# 12-JLINK_1.net
KiCad netlist of a schematic drawn in Altium Designer
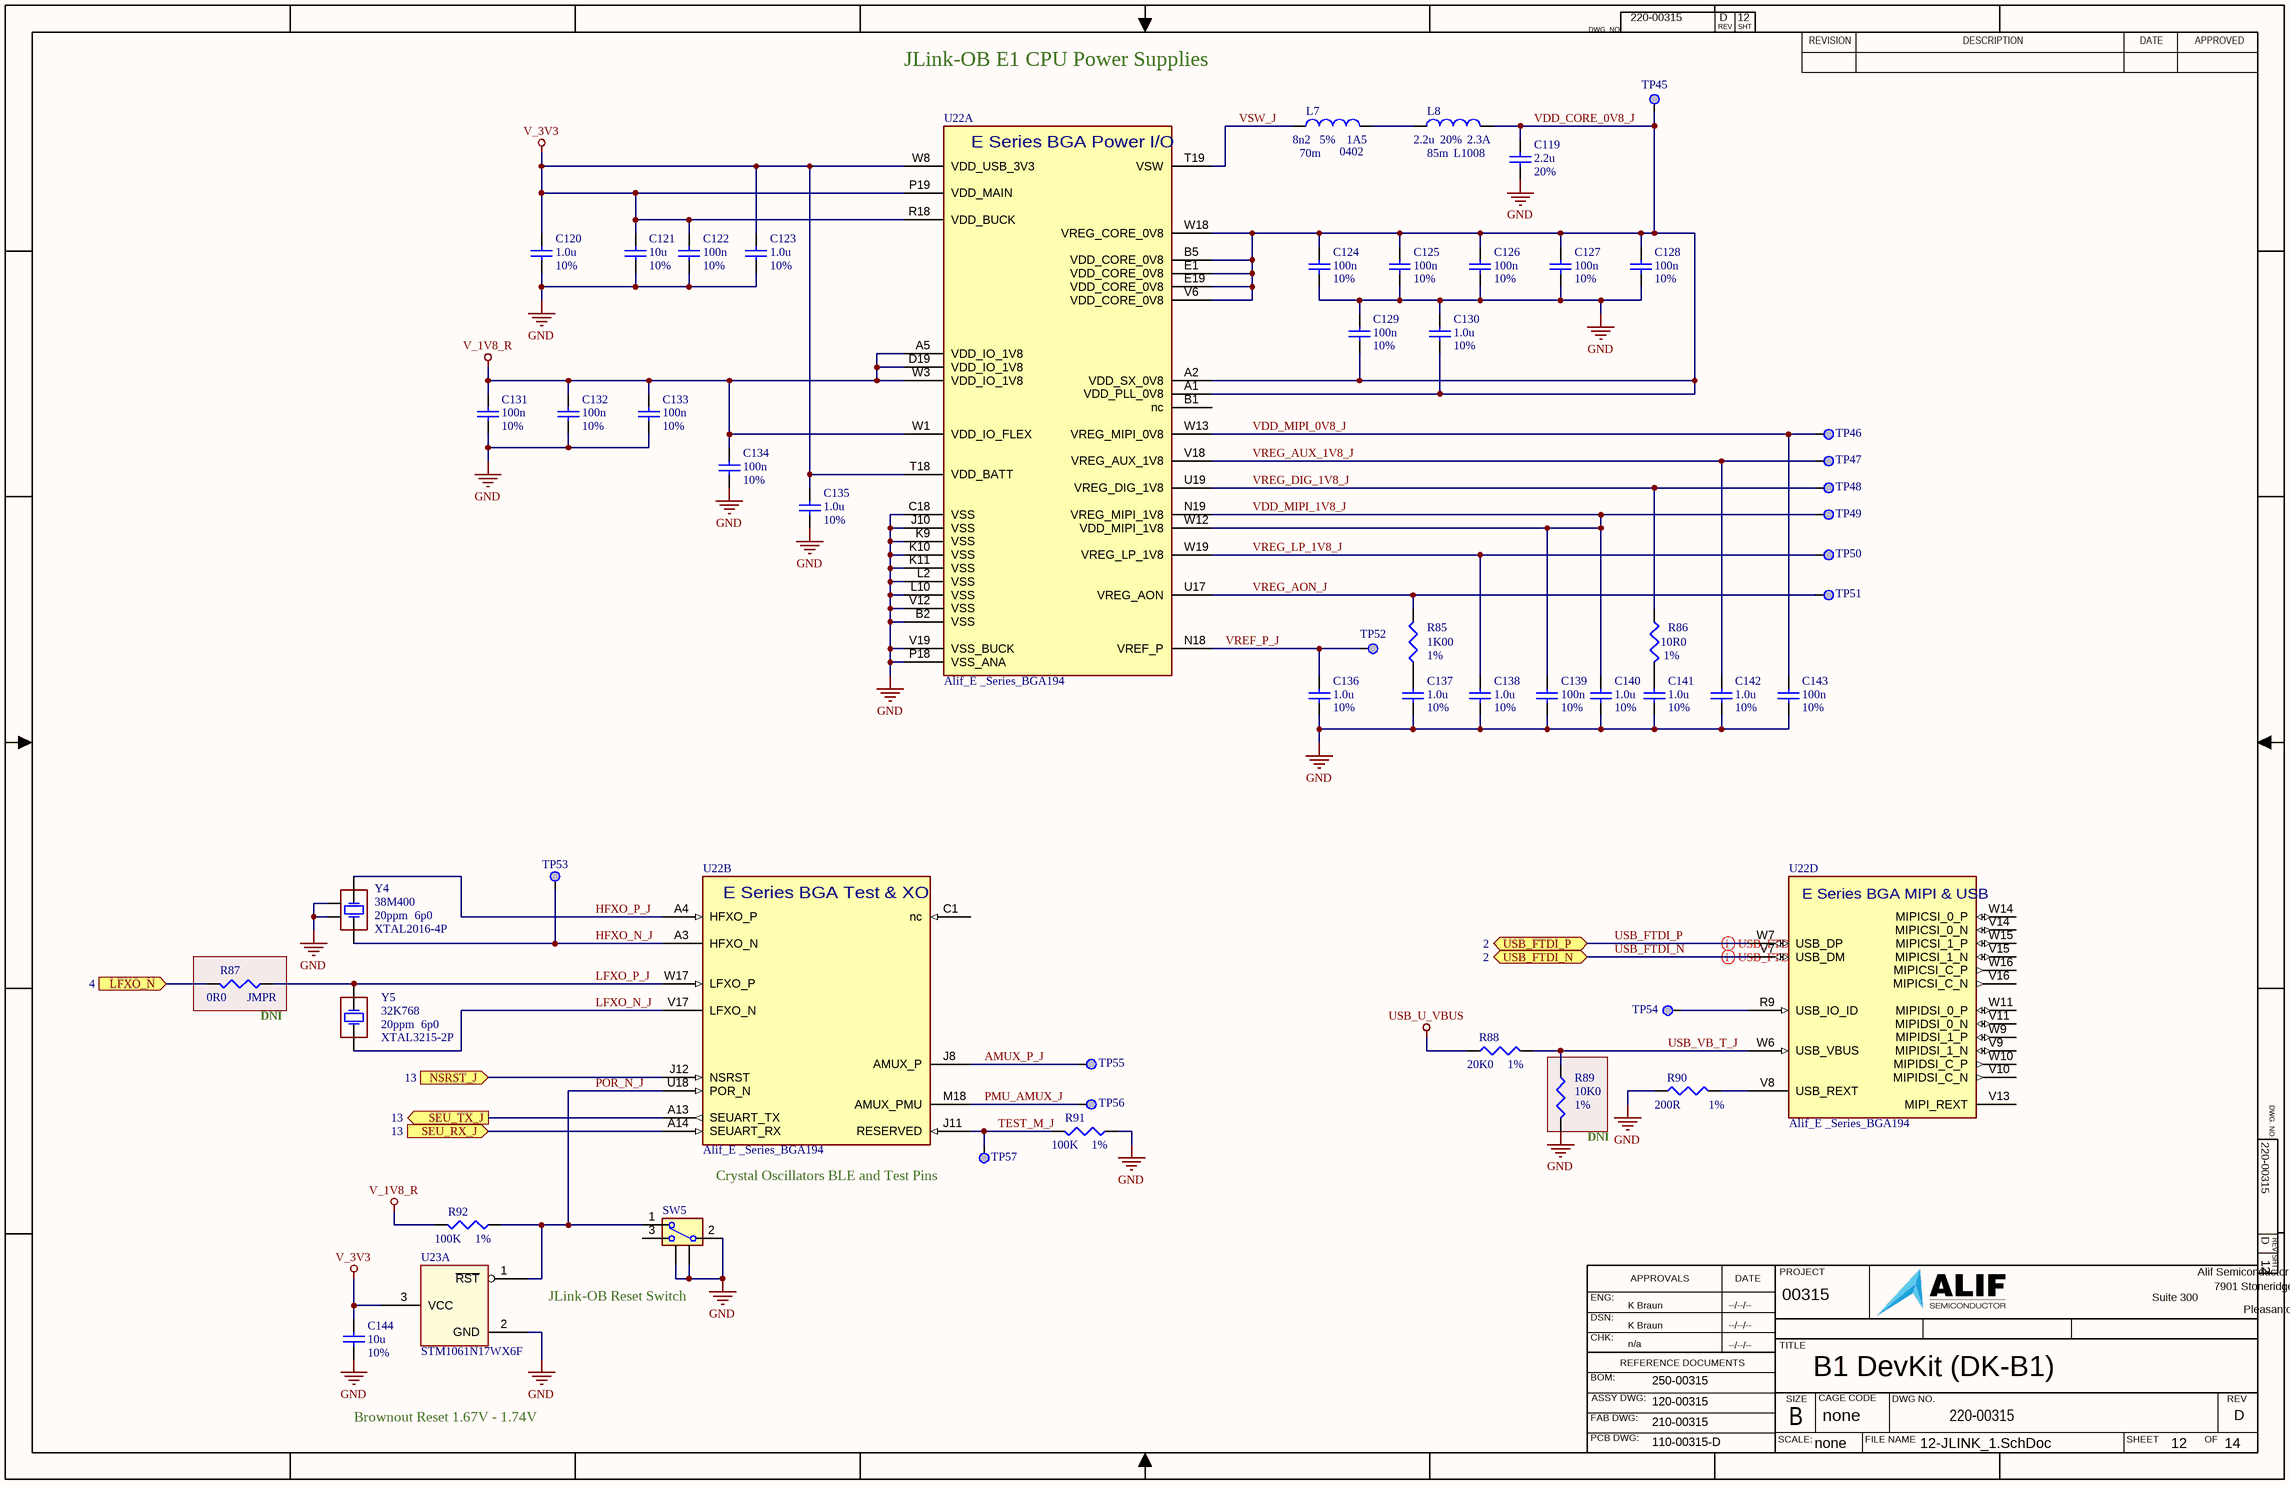
[diagram p0: 12-JLINK_1.SchDoc]

(export (version "E")
  (design (tool "Eeschema 10.0.6"))
  (components
    (comp (ref "C119")
      (value "2.2u")
      (footprint "CAPC0402-01")
      (description "Cap,2.2uF,20%,25V,X5R,0402")
      (fields
        (field (name "VOLTAGE") "25V")
        (field (name "TOLERANCE") "20%")
        (field (name "Comment") "Cap_225M25VX5R0402_1")
        (field (name "PUBLISHER") "Altium Limited")
      )
      (libsource (lib "Alif-2") (part "Cap_225M25VX5R0402_1"))
    )
    (comp (ref "C120")
      (value "1.0u")
      (footprint "CAPC0402-01")
      (description "Cap,1.0uF,20%,25V,X5R,0402")
      (fields
        (field (name "VOLTAGE") "25V")
        (field (name "TOLERANCE") "10%")
        (field (name "Comment") "Cap")
        (field (name "PUBLISHER") "Altium Limited")
      )
      (libsource (lib "kb1") (part "Cap"))
    )
    (comp (ref "C121")
      (value "10u")
      (footprint "CAPC0402-01")
      (description "Cap,10uF,20%,10V,X5R,0402")
      (fields
        (field (name "VOLTAGE") "10V")
        (field (name "TOLERANCE") "10%")
        (field (name "Comment") "Cap")
        (field (name "PUBLISHER") "Altium Limited")
      )
      (libsource (lib "kb1") (part "Cap"))
    )
    (comp (ref "C122")
      (value "100n")
      (footprint "CAPC0402-01")
      (description "Cap,100nF,10%,50V,X7R,0402")
      (fields
        (field (name "VOLTAGE") "50V")
        (field (name "TOLERANCE") "10%")
        (field (name "Comment") "Cap")
        (field (name "PUBLISHER") "Altium Limited")
      )
      (libsource (lib "kb1") (part "Cap"))
    )
    (comp (ref "C123")
      (value "1.0u")
      (footprint "CAPC0402-01")
      (description "Cap,1.0uF,20%,25V,X5R,0402")
      (fields
        (field (name "VOLTAGE") "25V")
        (field (name "TOLERANCE") "10%")
        (field (name "Comment") "Cap")
        (field (name "PUBLISHER") "Altium Limited")
      )
      (libsource (lib "kb1") (part "Cap"))
    )
    (comp (ref "C124")
      (value "100n")
      (footprint "CAPC0402-01")
      (description "Cap,100nF,10%,50V,X7R,0402")
      (fields
        (field (name "VOLTAGE") "50V")
        (field (name "TOLERANCE") "10%")
        (field (name "Comment") "Cap")
        (field (name "PUBLISHER") "Altium Limited")
      )
      (libsource (lib "kb1") (part "Cap"))
    )
    (comp (ref "C125")
      (value "100n")
      (footprint "CAPC0402-01")
      (description "Cap,100nF,10%,50V,X7R,0402")
      (fields
        (field (name "VOLTAGE") "50V")
        (field (name "TOLERANCE") "10%")
        (field (name "Comment") "Cap")
        (field (name "PUBLISHER") "Altium Limited")
      )
      (libsource (lib "kb1") (part "Cap"))
    )
    (comp (ref "C126")
      (value "100n")
      (footprint "CAPC0402-01")
      (description "Cap,100nF,10%,50V,X7R,0402")
      (fields
        (field (name "VOLTAGE") "50V")
        (field (name "TOLERANCE") "10%")
        (field (name "Comment") "Cap")
        (field (name "PUBLISHER") "Altium Limited")
      )
      (libsource (lib "kb1") (part "Cap"))
    )
    (comp (ref "C127")
      (value "100n")
      (footprint "CAPC0402-01")
      (description "Cap,100nF,10%,50V,X7R,0402")
      (fields
        (field (name "VOLTAGE") "50V")
        (field (name "TOLERANCE") "10%")
        (field (name "Comment") "Cap")
        (field (name "PUBLISHER") "Altium Limited")
      )
      (libsource (lib "kb1") (part "Cap"))
    )
    (comp (ref "C128")
      (value "100n")
      (footprint "CAPC0402-01")
      (description "Cap,100nF,10%,50V,X7R,0402")
      (fields
        (field (name "VOLTAGE") "50V")
        (field (name "TOLERANCE") "10%")
        (field (name "Comment") "Cap")
        (field (name "PUBLISHER") "Altium Limited")
      )
      (libsource (lib "kb1") (part "Cap"))
    )
    (comp (ref "C129")
      (value "100n")
      (footprint "CAPC0402-01")
      (description "Cap,100nF,10%,50V,X7R,0402")
      (fields
        (field (name "VOLTAGE") "50V")
        (field (name "TOLERANCE") "10%")
        (field (name "Comment") "Cap")
        (field (name "PUBLISHER") "Altium Limited")
      )
      (libsource (lib "kb1") (part "Cap"))
    )
    (comp (ref "C130")
      (value "1.0u")
      (footprint "CAPC0402-01")
      (description "Cap,1.0uF,20%,25V,X5R,0402")
      (fields
        (field (name "VOLTAGE") "25V")
        (field (name "TOLERANCE") "10%")
        (field (name "Comment") "Cap")
        (field (name "PUBLISHER") "Altium Limited")
      )
      (libsource (lib "kb1") (part "Cap"))
    )
    (comp (ref "C131")
      (value "100n")
      (footprint "CAPC0402-01")
      (description "Cap,100nF,10%,50V,X7R,0402")
      (fields
        (field (name "VOLTAGE") "50V")
        (field (name "TOLERANCE") "10%")
        (field (name "Comment") "Cap")
        (field (name "PUBLISHER") "Altium Limited")
      )
      (libsource (lib "kb1") (part "Cap"))
    )
    (comp (ref "C132")
      (value "100n")
      (footprint "CAPC0402-01")
      (description "Cap,100nF,10%,50V,X7R,0402")
      (fields
        (field (name "VOLTAGE") "50V")
        (field (name "TOLERANCE") "10%")
        (field (name "Comment") "Cap")
        (field (name "PUBLISHER") "Altium Limited")
      )
      (libsource (lib "kb1") (part "Cap"))
    )
    (comp (ref "C133")
      (value "100n")
      (footprint "CAPC0402-01")
      (description "Cap,100nF,10%,50V,X7R,0402")
      (fields
        (field (name "VOLTAGE") "50V")
        (field (name "TOLERANCE") "10%")
        (field (name "Comment") "Cap")
        (field (name "PUBLISHER") "Altium Limited")
      )
      (libsource (lib "kb1") (part "Cap"))
    )
    (comp (ref "C134")
      (value "100n")
      (footprint "CAPC0402-01")
      (description "Cap,100nF,10%,50V,X7R,0402")
      (fields
        (field (name "VOLTAGE") "50V")
        (field (name "TOLERANCE") "10%")
        (field (name "Comment") "Cap")
        (field (name "PUBLISHER") "Altium Limited")
      )
      (libsource (lib "kb1") (part "Cap"))
    )
    (comp (ref "C135")
      (value "1.0u")
      (footprint "CAPC0402-01")
      (description "Cap,1.0uF,20%,25V,X5R,0402")
      (fields
        (field (name "VOLTAGE") "25V")
        (field (name "TOLERANCE") "10%")
        (field (name "Comment") "Cap")
        (field (name "PUBLISHER") "Altium Limited")
      )
      (libsource (lib "kb1") (part "Cap"))
    )
    (comp (ref "C136")
      (value "1.0u")
      (footprint "CAPC0402-01")
      (description "Cap,1.0uF,20%,25V,X5R,0402")
      (fields
        (field (name "VOLTAGE") "25V")
        (field (name "TOLERANCE") "10%")
        (field (name "Comment") "Cap")
        (field (name "PUBLISHER") "Altium Limited")
      )
      (libsource (lib "kb1") (part "Cap"))
    )
    (comp (ref "C137")
      (value "1.0u")
      (footprint "CAPC0402-01")
      (description "Cap,1.0uF,20%,25V,X5R,0402")
      (fields
        (field (name "VOLTAGE") "25V")
        (field (name "TOLERANCE") "10%")
        (field (name "Comment") "Cap")
        (field (name "PUBLISHER") "Altium Limited")
      )
      (libsource (lib "kb1") (part "Cap"))
    )
    (comp (ref "C138")
      (value "1.0u")
      (footprint "CAPC0402-01")
      (description "Cap,1.0uF,20%,25V,X5R,0402")
      (fields
        (field (name "VOLTAGE") "25V")
        (field (name "TOLERANCE") "10%")
        (field (name "Comment") "Cap")
        (field (name "PUBLISHER") "Altium Limited")
      )
      (libsource (lib "kb1") (part "Cap"))
    )
    (comp (ref "C139")
      (value "100n")
      (footprint "CAPC0402-01")
      (description "Cap,100nF,10%,50V,X7R,0402")
      (fields
        (field (name "VOLTAGE") "50V")
        (field (name "TOLERANCE") "10%")
        (field (name "Comment") "Cap")
        (field (name "PUBLISHER") "Altium Limited")
      )
      (libsource (lib "kb1") (part "Cap"))
    )
    (comp (ref "C140")
      (value "1.0u")
      (footprint "CAPC0402-01")
      (description "Cap,1.0uF,20%,25V,X5R,0402")
      (fields
        (field (name "VOLTAGE") "25V")
        (field (name "TOLERANCE") "10%")
        (field (name "Comment") "Cap")
        (field (name "PUBLISHER") "Altium Limited")
      )
      (libsource (lib "kb1") (part "Cap"))
    )
    (comp (ref "C141")
      (value "1.0u")
      (footprint "CAPC0402-01")
      (description "Cap,1.0uF,20%,25V,X5R,0402")
      (fields
        (field (name "VOLTAGE") "25V")
        (field (name "TOLERANCE") "10%")
        (field (name "Comment") "Cap")
        (field (name "PUBLISHER") "Altium Limited")
      )
      (libsource (lib "kb1") (part "Cap"))
    )
    (comp (ref "C142")
      (value "1.0u")
      (footprint "CAPC0402-01")
      (description "Cap,1.0uF,20%,25V,X5R,0402")
      (fields
        (field (name "VOLTAGE") "25V")
        (field (name "TOLERANCE") "10%")
        (field (name "Comment") "Cap")
        (field (name "PUBLISHER") "Altium Limited")
      )
      (libsource (lib "kb1") (part "Cap"))
    )
    (comp (ref "C143")
      (value "100n")
      (footprint "CAPC0402-01")
      (description "Cap,100nF,10%,50V,X7R,0402")
      (fields
        (field (name "VOLTAGE") "50V")
        (field (name "TOLERANCE") "10%")
        (field (name "Comment") "Cap")
        (field (name "PUBLISHER") "Altium Limited")
      )
      (libsource (lib "kb1") (part "Cap"))
    )
    (comp (ref "C144")
      (value "10u")
      (footprint "CAPC0402-01")
      (description "Cap,10uF,20%,10V,X5R,0402")
      (fields
        (field (name "VOLTAGE") "10V")
        (field (name "TOLERANCE") "10%")
        (field (name "Comment") "Cap")
        (field (name "PUBLISHER") "Altium Limited")
      )
      (libsource (lib "kb1") (part "Cap"))
    )
    (comp (ref "L7")
      (value "8n2")
      (footprint "IND_WE-KI_0402")
      (description "Ind,Unshielded,8.2nH,<5%,1.5A,<70mOhm, SRF > 4GHz, 0402")
      (fields
        (field (name "PCB_FOOTPRINT") "0402")
        (field (name "DCR") "70m")
        (field (name "RMS_CURRENT") "1A5")
        (field (name "TOLERANCE") "5%")
        (field (name "Comment") "Inductor")
        (field (name "PUBLISHER") "Altium Limited")
      )
      (libsource (lib "Alif-2") (part "Inductor"))
    )
    (comp (ref "L8")
      (value "2.2u")
      (footprint "INDC2520X120N")
      (description "Ind,Unshielded,2.2uH,20%,2.3A,85mOhm,1008(2520)")
      (fields
        (field (name "PACKAGEREFERENCE") "L1008")
        (field (name "DCR") "85m")
        (field (name "RMS_CURRENT") "2.3A")
        (field (name "TOLERANCE") "20%")
        (field (name "Comment") "Inductor")
        (field (name "PUBLISHER") "Altium Limited")
      )
      (libsource (lib "Alif-2") (part "Inductor"))
    )
    (comp (ref "R85")
      (value "1K00")
      (footprint "RESC0402-01")
      (description "Res,1K00,1%,100ppm,0402")
      (fields
        (field (name "TOLERANCE") "1%")
        (field (name "Comment") "Res3")
        (field (name "PUBLISHER") "Altium Limited")
      )
      (libsource (lib "kb1") (part "Res3"))
    )
    (comp (ref "R86")
      (value "10R0")
      (footprint "RESC0402-01")
      (description "Res,10R0,1%,100ppm,0402")
      (fields
        (field (name "TOLERANCE") "1%")
        (field (name "Comment") "Res3")
        (field (name "PUBLISHER") "Altium Limited")
      )
      (libsource (lib "kb1") (part "Res3"))
    )
    (comp (ref "R87")
      (value "0R0")
      (footprint "RESC0402-01")
      (description "DNI,Res,0R ohm,Jumper,0402")
      (fields
        (field (name "TOLERANCE") "JMPR")
        (field (name "Comment") "Res3")
        (field (name "PUBLISHER") "Altium Limited")
      )
      (libsource (lib "kb1") (part "Res3"))
    )
    (comp (ref "R88")
      (value "20K0")
      (footprint "RESC0402-01")
      (description "Res,20K0,1%,100ppm,0402")
      (fields
        (field (name "TOLERANCE") "1%")
        (field (name "Comment") "Res3")
        (field (name "PUBLISHER") "Altium Limited")
      )
      (libsource (lib "kb1") (part "Res3"))
    )
    (comp (ref "R89")
      (value "10K0")
      (footprint "RESC0402-01")
      (description "DNI,Res,10K0,1%,100ppm,0402")
      (fields
        (field (name "TOLERANCE") "1%")
        (field (name "Comment") "Res3")
        (field (name "PUBLISHER") "Altium Limited")
      )
      (libsource (lib "kb1") (part "Res3"))
    )
    (comp (ref "R90")
      (value "200R")
      (footprint "RESC0402-01")
      (description "Res,200R,1%,100ppm,0402")
      (fields
        (field (name "TOLERANCE") "1%")
        (field (name "Comment") "Res3")
        (field (name "PUBLISHER") "Altium Limited")
      )
      (libsource (lib "kb1") (part "Res3"))
    )
    (comp (ref "R91")
      (value "100K")
      (footprint "RESC0402-01")
      (description "Res,100K,1%,100ppm,0402")
      (fields
        (field (name "TOLERANCE") "1%")
        (field (name "Comment") "Res3")
        (field (name "PUBLISHER") "Altium Limited")
      )
      (libsource (lib "kb1") (part "Res3"))
    )
    (comp (ref "R92")
      (value "100K")
      (footprint "RESC0402-01")
      (description "Res,100K,1%,100ppm,0402")
      (fields
        (field (name "TOLERANCE") "1%")
        (field (name "Comment") "Res3")
        (field (name "PUBLISHER") "Altium Limited")
      )
      (libsource (lib "kb1") (part "Res3"))
    )
    (comp (ref "SW5")
      (value "SPDT")
      (footprint "SW_SPDT_OS10201MSQN1")
      (description "Switch,SPDT, 12V, 50mA, Non-Shorting, 5 Pin PCB Vertical")
      (fields (field (name "PUBLISHER") "Altium Limited"))
      (libsource (lib "Alif-2") (part "SW-SPDT_Vert-5P"))
    )
    (comp (ref "TP45")
      (value "TP_SMPAD")
      (footprint "TP_30_RND")
      (description "Test Point, SMT Pad,--not a BOM item--")
      (libsource (lib "Alif-2") (part "TP_SMPAD"))
    )
    (comp (ref "TP46")
      (value "TP_SMPAD")
      (footprint "TP_30_RND")
      (description "Test Point, SMT Pad,--not a BOM item--")
      (libsource (lib "Alif-2") (part "TP_SMPAD"))
    )
    (comp (ref "TP47")
      (value "TP_SMPAD")
      (footprint "TP_30_RND")
      (description "Test Point, SMT Pad,--not a BOM item--")
      (libsource (lib "Alif-2") (part "TP_SMPAD"))
    )
    (comp (ref "TP48")
      (value "TP_SMPAD")
      (footprint "TP_30_RND")
      (description "Test Point, SMT Pad,--not a BOM item--")
      (libsource (lib "Alif-2") (part "TP_SMPAD"))
    )
    (comp (ref "TP49")
      (value "TP_SMPAD")
      (footprint "TP_30_RND")
      (description "Test Point, SMT Pad,--not a BOM item--")
      (libsource (lib "Alif-2") (part "TP_SMPAD"))
    )
    (comp (ref "TP50")
      (value "TP_SMPAD")
      (footprint "TP_30_RND")
      (description "Test Point, SMT Pad,--not a BOM item--")
      (libsource (lib "Alif-2") (part "TP_SMPAD"))
    )
    (comp (ref "TP51")
      (value "TP_SMPAD")
      (footprint "TP_30_RND")
      (description "Test Point, SMT Pad,--not a BOM item--")
      (libsource (lib "Alif-2") (part "TP_SMPAD"))
    )
    (comp (ref "TP52")
      (value "TP_SMPAD")
      (footprint "TP_30_RND")
      (description "Test Point, SMT Pad,--not a BOM item--")
      (libsource (lib "Alif-2") (part "TP_SMPAD"))
    )
    (comp (ref "TP53")
      (value "TP_SMPAD")
      (footprint "TP_30_RND")
      (description "Test Point, SMT Pad,--not a BOM item--")
      (libsource (lib "Alif-2") (part "TP_SMPAD"))
    )
    (comp (ref "TP54")
      (value "TP_SMPAD")
      (footprint "TP_30_RND")
      (description "Test Point, SMT Pad,--not a BOM item--")
      (libsource (lib "Alif-2") (part "TP_SMPAD"))
    )
    (comp (ref "TP55")
      (value "TP_SMPAD")
      (footprint "TP_30_RND")
      (description "Test Point, SMT Pad,--not a BOM item--")
      (libsource (lib "Alif-2") (part "TP_SMPAD"))
    )
    (comp (ref "TP56")
      (value "TP_SMPAD")
      (footprint "TP_30_RND")
      (description "Test Point, SMT Pad,--not a BOM item--")
      (libsource (lib "Alif-2") (part "TP_SMPAD"))
    )
    (comp (ref "TP57")
      (value "TP_SMPAD")
      (footprint "TP_30_RND")
      (description "Test Point, SMT Pad,--not a BOM item--")
      (libsource (lib "Alif-2") (part "TP_SMPAD"))
    )
    (comp (ref "U22")
      (value "Alif_E _Series_BGA194")
      (footprint "BGA194 _CENTERED")
      (description "IC,Alif E1 MCU, Rev B silicon,BGA194")
      (libsource (lib "Alif") (part "E7_B0_194BGA"))
    )
    (comp (ref "U23")
      (value "STM1061N17WX6F")
      (footprint "SOT-23_DBZ_TEX")
      (description "IC,PMIC Volt Supervisor, -Reset OD, 1.7V, 2%, 900nA, SOT23-3")
      (libsource (lib "Alif-2") (part "IC_SUP_STM1061N17WX6F"))
    )
    (comp (ref "Y4")
      (value "38M400")
      (footprint "OSC_4p_2016_XRCGB38M400F2P00R0")
      (description "Crystal,38.4MHz,20ppm,6.0pF,100ohm,2016-4pin")
      (fields
        (field (name "PCB_FOOTPRINT") "XTAL2016-4P")
        (field (name "PPM") "20ppm")
        (field (name "LOAD CAP") "6p0")
        (field (name "Comment") "Xtal_38M4_20PPM6PF_2016-4P_1")
        (field (name "PUBLISHER") "Altium Limited")
      )
      (libsource (lib "Alif-2") (part "Xtal_38M4_20PPM6PF_2016-4P_1"))
    )
    (comp (ref "Y5")
      (value "32K768")
      (footprint "XTAL_ABS07_ABR-M")
      (description "Crystal, 32.768KHz, 20ppm, 6pF, <70Kohm, 3215-2pin")
      (fields
        (field (name "PCB_FOOTPRINT") "XTAL3215-2P")
        (field (name "PPM") "20ppm")
        (field (name "LOAD CAP") "6p0")
        (field (name "Comment") "Xtal_32K768_20PPM6PF_3215-2P_1")
        (field (name "PUBLISHER") "Altium Limited")
      )
      (libsource (lib "Alif-2") (part "Xtal_32K768_20PPM6PF_3215-2P_1"))
    )
  )
  (nets
    (net (code "1") (name "/AMUX_P_J") (class "Default")
      (node (ref "TP55") (pin "1") (pinfunction "1_1") (pintype "passive"))
      (node (ref "U22") (pin "J8") (pinfunction "AMUX_P_J8") (pintype "passive"))
    )
    (net (code "2") (name "/HFXO_N_J") (class "Default")
      (node (ref "TP53") (pin "1") (pinfunction "1_1") (pintype "passive"))
      (node (ref "U22") (pin "A3") (pinfunction "HFXO_N_A3") (pintype "passive"))
      (node (ref "Y4") (pin "3") (pinfunction "OSC2_3") (pintype "passive"))
    )
    (net (code "3") (name "/HFXO_P_J") (class "Default")
      (node (ref "U22") (pin "A4") (pinfunction "HFXO_P_A4") (pintype "input"))
      (node (ref "Y4") (pin "1") (pinfunction "OSC1_1") (pintype "passive"))
    )
    (net (code "4") (name "/LFXO_N") (class "Default")
      (node (ref "R87") (pin "2") (pinfunction "2_2") (pintype "passive"))
    )
    (net (code "5") (name "/LFXO_N_J") (class "Default")
      (node (ref "U22") (pin "V17") (pinfunction "LFXO_N_V17") (pintype "passive"))
      (node (ref "Y5") (pin "1") (pinfunction "OSC1_1") (pintype "passive"))
    )
    (net (code "6") (name "/LFXO_P_J") (class "Default")
      (node (ref "R87") (pin "1") (pinfunction "1_1") (pintype "passive"))
      (node (ref "U22") (pin "W17") (pinfunction "LFXO_P_W17") (pintype "input"))
      (node (ref "Y5") (pin "2") (pinfunction "OSC2_2") (pintype "passive"))
    )
    (net (code "7") (name "/NSRST_J") (class "Default")
      (node (ref "U22") (pin "J12") (pinfunction "NSRST_J12") (pintype "input"))
    )
    (net (code "8") (name "/PMU_AMUX_J") (class "Default")
      (node (ref "TP56") (pin "1") (pinfunction "1_1") (pintype "passive"))
      (node (ref "U22") (pin "M18") (pinfunction "AMUX_PMU_M18") (pintype "passive"))
    )
    (net (code "9") (name "/POR_N_J") (class "Default")
      (node (ref "R92") (pin "1") (pinfunction "1_1") (pintype "passive"))
      (node (ref "SW5") (pin "1") (pinfunction "NC_1") (pintype "passive"))
      (node (ref "U22") (pin "U18") (pinfunction "POR_N_U18") (pintype "input"))
      (node (ref "U23") (pin "1") (pinfunction "~{RST}_1") (pintype "open_collector"))
    )
    (net (code "10") (name "/SEU_RX_J") (class "Default")
      (node (ref "U22") (pin "A14") (pinfunction "SEUART_RX_A14") (pintype "input"))
    )
    (net (code "11") (name "/SEU_TX_J") (class "Default")
      (node (ref "U22") (pin "A13") (pinfunction "SEUART_TX_A13") (pintype "output"))
    )
    (net (code "12") (name "/TEST_M_J") (class "Default")
      (node (ref "R91") (pin "2") (pinfunction "2_2") (pintype "passive"))
      (node (ref "TP57") (pin "1") (pinfunction "1_1") (pintype "passive"))
      (node (ref "U22") (pin "J11") (pinfunction "RESERVED_J11") (pintype "input"))
    )
    (net (code "13") (name "/USB_FTDI_N") (class "Default")
      (node (ref "U22") (pin "V7") (pinfunction "USB_DM_V7") (pintype "bidirectional"))
    )
    (net (code "14") (name "/USB_FTDI_P") (class "Default")
      (node (ref "U22") (pin "W7") (pinfunction "USB_DP_W7") (pintype "bidirectional"))
    )
    (net (code "15") (name "/USB_VB_T_J") (class "Default")
      (node (ref "R88") (pin "2") (pinfunction "2_2") (pintype "passive"))
      (node (ref "R89") (pin "1") (pinfunction "1_1") (pintype "passive"))
      (node (ref "U22") (pin "W6") (pinfunction "USB_VBUS_W6") (pintype "input"))
    )
    (net (code "16") (name "/VDD_CORE_0V8_J") (class "Default")
      (node (ref "C119") (pin "2") (pinfunction "2_2") (pintype "passive"))
      (node (ref "C124") (pin "2") (pinfunction "2_2") (pintype "passive"))
      (node (ref "C125") (pin "2") (pinfunction "2_2") (pintype "passive"))
      (node (ref "C126") (pin "2") (pinfunction "2_2") (pintype "passive"))
      (node (ref "C127") (pin "2") (pinfunction "2_2") (pintype "passive"))
      (node (ref "C128") (pin "2") (pinfunction "2_2") (pintype "passive"))
      (node (ref "C129") (pin "1") (pinfunction "1_1") (pintype "passive"))
      (node (ref "C130") (pin "1") (pinfunction "1_1") (pintype "passive"))
      (node (ref "L8") (pin "2") (pinfunction "2_2") (pintype "passive"))
      (node (ref "TP45") (pin "1") (pinfunction "1_1") (pintype "passive"))
      (node (ref "U22") (pin "A1") (pinfunction "VDD_PLL_0V8_A1") (pintype "power_in"))
      (node (ref "U22") (pin "A2") (pinfunction "VDD_SX_0V8_A2") (pintype "power_in"))
      (node (ref "U22") (pin "B5") (pinfunction "VDD_CORE_0V8_B5") (pintype "power_in"))
      (node (ref "U22") (pin "E1") (pinfunction "VDD_CORE_0V8_E1") (pintype "power_in"))
      (node (ref "U22") (pin "E19") (pinfunction "VDD_CORE_0V8_E19") (pintype "power_in"))
      (node (ref "U22") (pin "V6") (pinfunction "VDD_CORE_0V8_V6") (pintype "power_in"))
      (node (ref "U22") (pin "W18") (pinfunction "VREG_CORE_0V8_W18") (pintype "power_in"))
    )
    (net (code "17") (name "/VDD_MIPI_0V8_J") (class "Default")
      (node (ref "C143") (pin "2") (pinfunction "2_2") (pintype "passive"))
      (node (ref "TP46") (pin "1") (pinfunction "1_1") (pintype "passive"))
      (node (ref "U22") (pin "W13") (pinfunction "VREG_MIPI_0V8_W13") (pintype "power_in"))
    )
    (net (code "18") (name "/VDD_MIPI_1V8_J") (class "Default")
      (node (ref "C139") (pin "2") (pinfunction "2_2") (pintype "passive"))
      (node (ref "C140") (pin "2") (pinfunction "2_2") (pintype "passive"))
      (node (ref "TP49") (pin "1") (pinfunction "1_1") (pintype "passive"))
      (node (ref "U22") (pin "N19") (pinfunction "VREG_MIPI_1V8_N19") (pintype "power_in"))
      (node (ref "U22") (pin "W12") (pinfunction "VDD_MIPI_1V8_W12") (pintype "power_in"))
    )
    (net (code "19") (name "/VREF_P_J") (class "Default")
      (node (ref "C136") (pin "2") (pinfunction "2_2") (pintype "passive"))
      (node (ref "TP52") (pin "1") (pinfunction "1_1") (pintype "passive"))
      (node (ref "U22") (pin "N18") (pinfunction "VREF_P_N18") (pintype "passive"))
    )
    (net (code "20") (name "/VREG_AON_J") (class "Default")
      (node (ref "R85") (pin "2") (pinfunction "2_2") (pintype "passive"))
      (node (ref "TP51") (pin "1") (pinfunction "1_1") (pintype "passive"))
      (node (ref "U22") (pin "U17") (pinfunction "VREG_AON_U17") (pintype "power_in"))
    )
    (net (code "21") (name "/VREG_AUX_1V8_J") (class "Default")
      (node (ref "C142") (pin "2") (pinfunction "2_2") (pintype "passive"))
      (node (ref "TP47") (pin "1") (pinfunction "1_1") (pintype "passive"))
      (node (ref "U22") (pin "V18") (pinfunction "VREG_AUX_1V8_V18") (pintype "power_in"))
    )
    (net (code "22") (name "/VREG_DIG_1V8_J") (class "Default")
      (node (ref "R86") (pin "2") (pinfunction "2_2") (pintype "passive"))
      (node (ref "TP48") (pin "1") (pinfunction "1_1") (pintype "passive"))
      (node (ref "U22") (pin "U19") (pinfunction "VREG_DIG_1V8_U19") (pintype "power_in"))
    )
    (net (code "23") (name "/VREG_LP_1V8_J") (class "Default")
      (node (ref "C138") (pin "2") (pinfunction "2_2") (pintype "passive"))
      (node (ref "TP50") (pin "1") (pinfunction "1_1") (pintype "passive"))
      (node (ref "U22") (pin "W19") (pinfunction "VREG_LP_1V8_W19") (pintype "power_in"))
    )
    (net (code "24") (name "/VSW_J") (class "Default")
      (node (ref "L7") (pin "1") (pinfunction "1_1") (pintype "passive"))
      (node (ref "U22") (pin "T19") (pinfunction "VSW_T19") (pintype "passive"))
    )
    (net (code "25") (name "GND") (class "Default")
      (node (ref "C119") (pin "1") (pinfunction "1_1") (pintype "passive"))
      (node (ref "C120") (pin "1") (pinfunction "1_1") (pintype "passive"))
      (node (ref "C121") (pin "1") (pinfunction "1_1") (pintype "passive"))
      (node (ref "C122") (pin "1") (pinfunction "1_1") (pintype "passive"))
      (node (ref "C123") (pin "1") (pinfunction "1_1") (pintype "passive"))
      (node (ref "C124") (pin "1") (pinfunction "1_1") (pintype "passive"))
      (node (ref "C125") (pin "1") (pinfunction "1_1") (pintype "passive"))
      (node (ref "C126") (pin "1") (pinfunction "1_1") (pintype "passive"))
      (node (ref "C127") (pin "1") (pinfunction "1_1") (pintype "passive"))
      (node (ref "C128") (pin "1") (pinfunction "1_1") (pintype "passive"))
      (node (ref "C129") (pin "2") (pinfunction "2_2") (pintype "passive"))
      (node (ref "C130") (pin "2") (pinfunction "2_2") (pintype "passive"))
      (node (ref "C131") (pin "1") (pinfunction "1_1") (pintype "passive"))
      (node (ref "C132") (pin "1") (pinfunction "1_1") (pintype "passive"))
      (node (ref "C133") (pin "1") (pinfunction "1_1") (pintype "passive"))
      (node (ref "C134") (pin "1") (pinfunction "1_1") (pintype "passive"))
      (node (ref "C135") (pin "1") (pinfunction "1_1") (pintype "passive"))
      (node (ref "C136") (pin "1") (pinfunction "1_1") (pintype "passive"))
      (node (ref "C137") (pin "1") (pinfunction "1_1") (pintype "passive"))
      (node (ref "C138") (pin "1") (pinfunction "1_1") (pintype "passive"))
      (node (ref "C139") (pin "1") (pinfunction "1_1") (pintype "passive"))
      (node (ref "C140") (pin "1") (pinfunction "1_1") (pintype "passive"))
      (node (ref "C141") (pin "1") (pinfunction "1_1") (pintype "passive"))
      (node (ref "C142") (pin "1") (pinfunction "1_1") (pintype "passive"))
      (node (ref "C143") (pin "1") (pinfunction "1_1") (pintype "passive"))
      (node (ref "C144") (pin "1") (pinfunction "1_1") (pintype "passive"))
      (node (ref "R89") (pin "2") (pinfunction "2_2") (pintype "passive"))
      (node (ref "R90") (pin "1") (pinfunction "1_1") (pintype "passive"))
      (node (ref "R91") (pin "1") (pinfunction "1_1") (pintype "passive"))
      (node (ref "SW5") (pin "2") (pinfunction "COMMON_2") (pintype "passive"))
      (node (ref "SW5") (pin "4") (pinfunction "G1_4") (pintype "passive"))
      (node (ref "SW5") (pin "5") (pinfunction "G2_5") (pintype "passive"))
      (node (ref "U22") (pin "B2") (pinfunction "VSS_B2") (pintype "power_in"))
      (node (ref "U22") (pin "C18") (pinfunction "VSS_C18") (pintype "power_in"))
      (node (ref "U22") (pin "J10") (pinfunction "VSS_J10") (pintype "power_in"))
      (node (ref "U22") (pin "K10") (pinfunction "VSS_K10") (pintype "power_in"))
      (node (ref "U22") (pin "K11") (pinfunction "VSS_K11") (pintype "power_in"))
      (node (ref "U22") (pin "K9") (pinfunction "VSS_K9") (pintype "power_in"))
      (node (ref "U22") (pin "L10") (pinfunction "VSS_L10") (pintype "power_in"))
      (node (ref "U22") (pin "L2") (pinfunction "VSS_L2") (pintype "power_in"))
      (node (ref "U22") (pin "P18") (pinfunction "VSS_ANA_P18") (pintype "power_in"))
      (node (ref "U22") (pin "V12") (pinfunction "VSS_V12") (pintype "power_in"))
      (node (ref "U22") (pin "V19") (pinfunction "VSS_BUCK_V19") (pintype "power_in"))
      (node (ref "U23") (pin "2") (pinfunction "GND_2") (pintype "power_in"))
      (node (ref "Y4") (pin "2") (pinfunction "2_2") (pintype "passive"))
      (node (ref "Y4") (pin "4") (pinfunction "4_4") (pintype "passive"))
    )
    (net (code "26") (name "Net-(C137-Pad2)") (class "Default")
      (node (ref "C137") (pin "2") (pinfunction "2_2") (pintype "passive"))
      (node (ref "R85") (pin "1") (pinfunction "1_1") (pintype "passive"))
    )
    (net (code "27") (name "Net-(C141-Pad2)") (class "Default")
      (node (ref "C141") (pin "2") (pinfunction "2_2") (pintype "passive"))
      (node (ref "R86") (pin "1") (pinfunction "1_1") (pintype "passive"))
    )
    (net (code "28") (name "Net-(L7-Pad2)") (class "Default")
      (node (ref "L7") (pin "2") (pinfunction "2_2") (pintype "passive"))
      (node (ref "L8") (pin "1") (pinfunction "1_1") (pintype "passive"))
    )
    (net (code "29") (name "Net-(U22D-USB_IO_ID)") (class "Default")
      (node (ref "TP54") (pin "1") (pinfunction "1_1") (pintype "passive"))
      (node (ref "U22") (pin "R9") (pinfunction "USB_IO_ID_R9") (pintype "input"))
    )
    (net (code "30") (name "Net-(U22D-USB_REXT)") (class "Default")
      (node (ref "R90") (pin "2") (pinfunction "2_2") (pintype "passive"))
      (node (ref "U22") (pin "V8") (pinfunction "USB_REXT_V8") (pintype "passive"))
    )
    (net (code "31") (name "USB_U_VBUS") (class "Default")
      (node (ref "R88") (pin "1") (pinfunction "1_1") (pintype "passive"))
    )
    (net (code "32") (name "V_1V8_R") (class "Default")
      (node (ref "C131") (pin "2") (pinfunction "2_2") (pintype "passive"))
      (node (ref "C132") (pin "2") (pinfunction "2_2") (pintype "passive"))
      (node (ref "C133") (pin "2") (pinfunction "2_2") (pintype "passive"))
      (node (ref "C134") (pin "2") (pinfunction "2_2") (pintype "passive"))
      (node (ref "R92") (pin "2") (pinfunction "2_2") (pintype "passive"))
      (node (ref "U22") (pin "A5") (pinfunction "VDD_IO_1V8_A5") (pintype "power_in"))
      (node (ref "U22") (pin "D19") (pinfunction "VDD_IO_1V8_D19") (pintype "power_in"))
      (node (ref "U22") (pin "W1") (pinfunction "VDD_IO_FLEX_W1") (pintype "power_in"))
      (node (ref "U22") (pin "W3") (pinfunction "VDD_IO_1V8_W3") (pintype "power_in"))
    )
    (net (code "33") (name "V_3V3") (class "Default")
      (node (ref "C120") (pin "2") (pinfunction "2_2") (pintype "passive"))
      (node (ref "C121") (pin "2") (pinfunction "2_2") (pintype "passive"))
      (node (ref "C122") (pin "2") (pinfunction "2_2") (pintype "passive"))
      (node (ref "C123") (pin "2") (pinfunction "2_2") (pintype "passive"))
      (node (ref "C135") (pin "2") (pinfunction "2_2") (pintype "passive"))
      (node (ref "C144") (pin "2") (pinfunction "2_2") (pintype "passive"))
      (node (ref "U22") (pin "P19") (pinfunction "VDD_MAIN_P19") (pintype "power_in"))
      (node (ref "U22") (pin "R18") (pinfunction "VDD_BUCK_R18") (pintype "power_in"))
      (node (ref "U22") (pin "T18") (pinfunction "VDD_BATT_T18") (pintype "power_in"))
      (node (ref "U22") (pin "W8") (pinfunction "VDD_USB_3V3_W8") (pintype "power_in"))
      (node (ref "U23") (pin "3") (pinfunction "VCC_3") (pintype "power_in"))
    )
    (net (code "34") (name "unconnected-(SW5-NO-Pad3)") (class "Default")
      (node (ref "SW5") (pin "3") (pinfunction "NO_3") (pintype "passive"))
    )
    (net (code "35") (name "unconnected-(U22A-nc-PadB1)") (class "Default")
      (node (ref "U22") (pin "B1") (pinfunction "nc_B1") (pintype "power_in"))
    )
    (net (code "36") (name "unconnected-(U22B-nc-PadC1)") (class "Default")
      (node (ref "U22") (pin "C1") (pinfunction "nc_C1") (pintype "input"))
    )
    (net (code "37") (name "unconnected-(U22D-MIPICSI_0_N-PadV14)") (class "Default")
      (node (ref "U22") (pin "V14") (pinfunction "MIPICSI_0_N_V14") (pintype "bidirectional"))
    )
    (net (code "38") (name "unconnected-(U22D-MIPICSI_0_P-PadW14)") (class "Default")
      (node (ref "U22") (pin "W14") (pinfunction "MIPICSI_0_P_W14") (pintype "bidirectional"))
    )
    (net (code "39") (name "unconnected-(U22D-MIPICSI_1_N-PadV15)") (class "Default")
      (node (ref "U22") (pin "V15") (pinfunction "MIPICSI_1_N_V15") (pintype "bidirectional"))
    )
    (net (code "40") (name "unconnected-(U22D-MIPICSI_1_P-PadW15)") (class "Default")
      (node (ref "U22") (pin "W15") (pinfunction "MIPICSI_1_P_W15") (pintype "bidirectional"))
    )
    (net (code "41") (name "unconnected-(U22D-MIPICSI_C_N-PadV16)") (class "Default")
      (node (ref "U22") (pin "V16") (pinfunction "MIPICSI_C_N_V16") (pintype "output"))
    )
    (net (code "42") (name "unconnected-(U22D-MIPICSI_C_P-PadW16)") (class "Default")
      (node (ref "U22") (pin "W16") (pinfunction "MIPICSI_C_P_W16") (pintype "output"))
    )
    (net (code "43") (name "unconnected-(U22D-MIPIDSI_0_N-PadV11)") (class "Default")
      (node (ref "U22") (pin "V11") (pinfunction "MIPIDSI_0_N_V11") (pintype "bidirectional"))
    )
    (net (code "44") (name "unconnected-(U22D-MIPIDSI_0_P-PadW11)") (class "Default")
      (node (ref "U22") (pin "W11") (pinfunction "MIPIDSI_0_P_W11") (pintype "bidirectional"))
    )
    (net (code "45") (name "unconnected-(U22D-MIPIDSI_1_N-PadV9)") (class "Default")
      (node (ref "U22") (pin "V9") (pinfunction "MIPIDSI_1_N_V9") (pintype "bidirectional"))
    )
    (net (code "46") (name "unconnected-(U22D-MIPIDSI_1_P-PadW9)") (class "Default")
      (node (ref "U22") (pin "W9") (pinfunction "MIPIDSI_1_P_W9") (pintype "bidirectional"))
    )
    (net (code "47") (name "unconnected-(U22D-MIPIDSI_C_N-PadV10)") (class "Default")
      (node (ref "U22") (pin "V10") (pinfunction "MIPIDSI_C_N_V10") (pintype "output"))
    )
    (net (code "48") (name "unconnected-(U22D-MIPIDSI_C_P-PadW10)") (class "Default")
      (node (ref "U22") (pin "W10") (pinfunction "MIPIDSI_C_P_W10") (pintype "output"))
    )
    (net (code "49") (name "unconnected-(U22D-MIPI_REXT-PadV13)") (class "Default")
      (node (ref "U22") (pin "V13") (pinfunction "MIPI_REXT_V13") (pintype "passive"))
    )
  )
)
